# Sheet2.net
KiCad netlist of a schematic drawn in Altium Designer
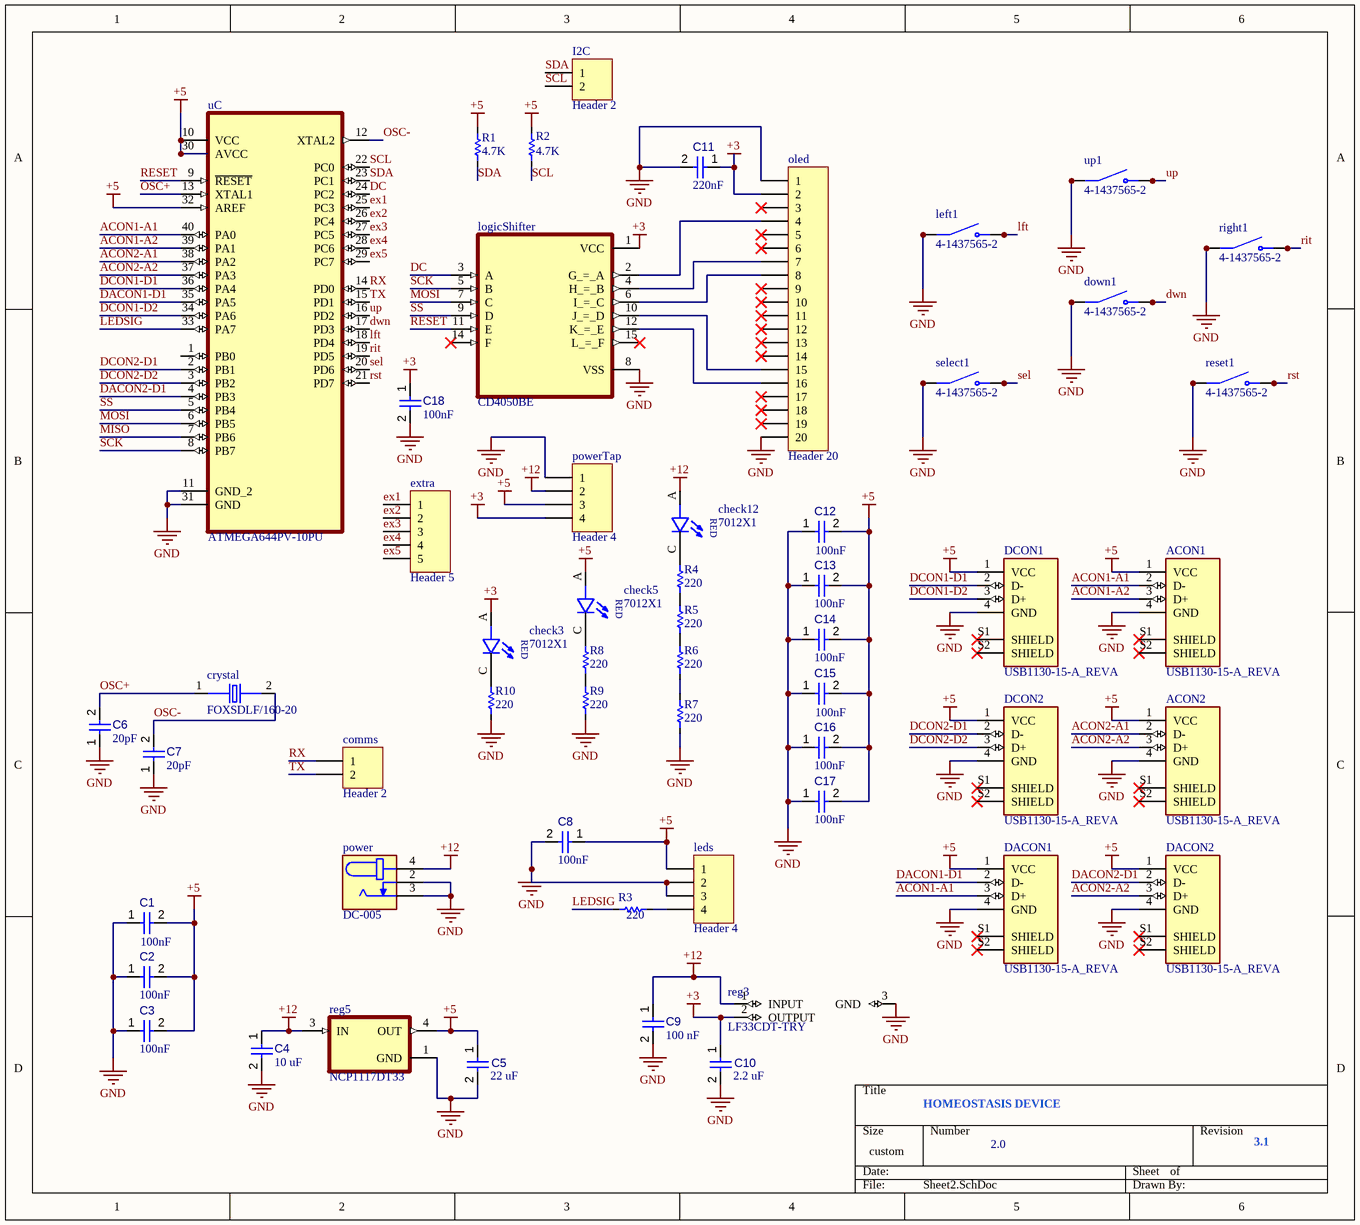
[diagram p0: Sheet2.SchDoc]

(export (version "E")
  (design (tool "Eeschema 10.0.6"))
  (components
    (comp (ref "ACON1")
      (value "USB1130-15-A_REVA")
      (footprint "GCT_USB1130-15-A_REVA")
      (fields (field (name "MF") "{'manufacturer': u'Global Connector Technology'}"))
      (libsource (lib "SnapEDA_Library") (part "USB1130-15-A_REVA"))
    )
    (comp (ref "ACON2")
      (value "USB1130-15-A_REVA")
      (footprint "GCT_USB1130-15-A_REVA")
      (fields (field (name "MF") "{'manufacturer': u'Global Connector Technology'}"))
      (libsource (lib "SnapEDA_Library") (part "USB1130-15-A_REVA"))
    )
    (comp (ref "C1")
      (value "100nF")
      (footprint "CAPC0805(2012)145_L")
      (description "Chip Capacitor, 4.7µF +/-40%, 25V, 0805, Thickness 1.45 mm")
      (fields (field (name "TOLERANCE") "20%") (field (name "Comment") "Capacitor 4.7µF +/-40% 25V 0805"))
      (libsource (lib "University of Minnesota - Solar Vehicle Project") (part "CAP-NP-2"))
    )
    (comp (ref "C2")
      (value "100nF")
      (footprint "CAPC0805(2012)145_L")
      (description "Chip Capacitor, 4.7µF +/-40%, 25V, 0805, Thickness 1.45 mm")
      (fields (field (name "TOLERANCE") "20%") (field (name "Comment") "Capacitor 4.7µF +/-40% 25V 0805"))
      (libsource (lib "University of Minnesota - Solar Vehicle Project") (part "CAP-NP-2"))
    )
    (comp (ref "C3")
      (value "100nF")
      (footprint "CAPC0805(2012)145_L")
      (description "Chip Capacitor, 4.7µF +/-40%, 25V, 0805, Thickness 1.45 mm")
      (fields (field (name "TOLERANCE") "20%") (field (name "Comment") "Capacitor 4.7µF +/-40% 25V 0805"))
      (libsource (lib "University of Minnesota - Solar Vehicle Project") (part "CAP-NP-2"))
    )
    (comp (ref "C4")
      (value "10 uF")
      (footprint "CAPC0805(2012)145_L")
      (description "Chip Capacitor, 4.7µF +/-40%, 25V, 0805, Thickness 1.45 mm")
      (fields (field (name "TOLERANCE") "20%") (field (name "Comment") "Capacitor 4.7µF +/-40% 25V 0805"))
      (libsource (lib "University of Minnesota - Solar Vehicle Project") (part "CAP-NP-2"))
    )
    (comp (ref "C5")
      (value "22 uF")
      (footprint "CAPC0805(2012)145_L")
      (description "Chip Capacitor, 4.7µF +/-40%, 25V, 0805, Thickness 1.45 mm")
      (fields (field (name "TOLERANCE") "20%") (field (name "Comment") "Capacitor 4.7µF +/-40% 25V 0805"))
      (libsource (lib "University of Minnesota - Solar Vehicle Project") (part "CAP-NP-2"))
    )
    (comp (ref "C6")
      (value "20pF")
      (footprint "CAPC2013X135X45ML10T25")
      (description "Chip Capacitor, 1 uF, +/- 10%, 50 V, 0805 (2012 Metric)")
      (fields (field (name "TOLERANCE") "10%") (field (name "Comment") "Capacitor 1 uF +/- 10% 50 V 0805"))
      (libsource (lib "University of Minnesota - Solar Vehicle Project") (part "CAP-NP-2"))
    )
    (comp (ref "C7")
      (value "20pF")
      (footprint "CAPC2013X135X45ML10T25")
      (description "Chip Capacitor, 1 uF, +/- 10%, 50 V, 0805 (2012 Metric)")
      (fields (field (name "TOLERANCE") "10%") (field (name "Comment") "Capacitor 1 uF +/- 10% 50 V 0805"))
      (libsource (lib "University of Minnesota - Solar Vehicle Project") (part "CAP-NP-2"))
    )
    (comp (ref "C8")
      (value "100nF")
      (footprint "CAPC0805(2012)145_L")
      (description "Chip Capacitor, 4.7µF +/-40%, 25V, 0805, Thickness 1.45 mm")
      (fields (field (name "TOLERANCE") "20%") (field (name "Comment") "Capacitor 4.7µF +/-40% 25V 0805"))
      (libsource (lib "University of Minnesota - Solar Vehicle Project") (part "CAP-NP-2"))
    )
    (comp (ref "C9")
      (value "100 nF")
      (footprint "CAPC0805(2012)145_L")
      (description "Chip Capacitor, 4.7µF +/-40%, 25V, 0805, Thickness 1.45 mm")
      (fields (field (name "TOLERANCE") "20%") (field (name "Comment") "Capacitor 4.7µF +/-40% 25V 0805"))
      (libsource (lib "University of Minnesota - Solar Vehicle Project") (part "CAP-NP-2"))
    )
    (comp (ref "C10")
      (value "2.2 uF")
      (footprint "CAPC0805(2012)145_L")
      (description "Chip Capacitor, 4.7µF +/-40%, 25V, 0805, Thickness 1.45 mm")
      (fields (field (name "TOLERANCE") "20%") (field (name "Comment") "Capacitor 4.7µF +/-40% 25V 0805"))
      (libsource (lib "University of Minnesota - Solar Vehicle Project") (part "CAP-NP-2"))
    )
    (comp (ref "C11")
      (value "220nF")
      (footprint "CAPC0805(2012)145_L")
      (description "Chip Capacitor, 4.7µF +/-40%, 25V, 0805, Thickness 1.45 mm")
      (fields (field (name "TOLERANCE") "20%") (field (name "Comment") "Capacitor 4.7µF +/-40% 25V 0805"))
      (libsource (lib "University of Minnesota - Solar Vehicle Project") (part "CAP-NP-2"))
    )
    (comp (ref "C12")
      (value "100nF")
      (footprint "CAPC0805(2012)145_L")
      (description "Chip Capacitor, 4.7µF +/-40%, 25V, 0805, Thickness 1.45 mm")
      (fields (field (name "TOLERANCE") "20%") (field (name "Comment") "Capacitor 4.7µF +/-40% 25V 0805"))
      (libsource (lib "University of Minnesota - Solar Vehicle Project") (part "CAP-NP-2"))
    )
    (comp (ref "C13")
      (value "100nF")
      (footprint "CAPC0805(2012)145_L")
      (description "Chip Capacitor, 4.7µF +/-40%, 25V, 0805, Thickness 1.45 mm")
      (fields (field (name "TOLERANCE") "20%") (field (name "Comment") "Capacitor 4.7µF +/-40% 25V 0805"))
      (libsource (lib "University of Minnesota - Solar Vehicle Project") (part "CAP-NP-2"))
    )
    (comp (ref "C14")
      (value "100nF")
      (footprint "CAPC0805(2012)145_L")
      (description "Chip Capacitor, 4.7µF +/-40%, 25V, 0805, Thickness 1.45 mm")
      (fields (field (name "TOLERANCE") "20%") (field (name "Comment") "Capacitor 4.7µF +/-40% 25V 0805"))
      (libsource (lib "University of Minnesota - Solar Vehicle Project") (part "CAP-NP-2"))
    )
    (comp (ref "C15")
      (value "100nF")
      (footprint "CAPC0805(2012)145_L")
      (description "Chip Capacitor, 4.7µF +/-40%, 25V, 0805, Thickness 1.45 mm")
      (fields (field (name "TOLERANCE") "20%") (field (name "Comment") "Capacitor 4.7µF +/-40% 25V 0805"))
      (libsource (lib "University of Minnesota - Solar Vehicle Project") (part "CAP-NP-2"))
    )
    (comp (ref "C16")
      (value "100nF")
      (footprint "CAPC0805(2012)145_L")
      (description "Chip Capacitor, 4.7µF +/-40%, 25V, 0805, Thickness 1.45 mm")
      (fields (field (name "TOLERANCE") "20%") (field (name "Comment") "Capacitor 4.7µF +/-40% 25V 0805"))
      (libsource (lib "University of Minnesota - Solar Vehicle Project") (part "CAP-NP-2"))
    )
    (comp (ref "C17")
      (value "100nF")
      (footprint "CAPC0805(2012)145_L")
      (description "Chip Capacitor, 4.7µF +/-40%, 25V, 0805, Thickness 1.45 mm")
      (fields (field (name "TOLERANCE") "20%") (field (name "Comment") "Capacitor 4.7µF +/-40% 25V 0805"))
      (libsource (lib "University of Minnesota - Solar Vehicle Project") (part "CAP-NP-2"))
    )
    (comp (ref "C18")
      (value "100nF")
      (footprint "CAPC0805(2012)145_L")
      (description "Chip Capacitor, 4.7µF +/-40%, 25V, 0805, Thickness 1.45 mm")
      (fields (field (name "TOLERANCE") "20%") (field (name "Comment") "Capacitor 4.7µF +/-40% 25V 0805"))
      (libsource (lib "University of Minnesota - Solar Vehicle Project") (part "CAP-NP-2"))
    )
    (comp (ref "check3")
      (value "7012X1")
      (footprint "LED_7012X1")
      (description "Red LED Indication - Discrete 1.7V 0805 (2012 Metric)")
      (fields (field (name "MF") "{'manufacturer': u'Visual'}"))
      (libsource (lib "SnapEDA_Library") (part "7012X1"))
    )
    (comp (ref "check5")
      (value "7012X1")
      (footprint "LED_7012X1")
      (description "Red LED Indication - Discrete 1.7V 0805 (2012 Metric)")
      (fields (field (name "MF") "{'manufacturer': u'Visual'}"))
      (libsource (lib "SnapEDA_Library") (part "7012X1"))
    )
    (comp (ref "check12")
      (value "7012X1")
      (footprint "LED_7012X1")
      (description "Red LED Indication - Discrete 1.7V 0805 (2012 Metric)")
      (fields (field (name "MF") "{'manufacturer': u'Visual'}"))
      (libsource (lib "SnapEDA_Library") (part "7012X1"))
    )
    (comp (ref "comms")
      (value "Header 2")
      (footprint "HDR1X2")
      (description "Header, 2-Pin")
      (fields (field (name "PUBLISHER") "Altium Limited"))
      (libsource (lib "Miscellaneous Connectors") (part "Header 2"))
    )
    (comp (ref "crystal")
      (value "FOXSDLF/160-20")
      (footprint "XTAL_FOXSDLF/160-20")
      (description "Crystal 16MHz 20pF 2-Pin HC-49/SD")
      (fields (field (name "MF") "{'manufacturer': u'Fox Electronics'}"))
      (libsource (lib "SnapEDA_Library") (part "FOXSDLF/160-20"))
    )
    (comp (ref "DACON1")
      (value "USB1130-15-A_REVA")
      (footprint "GCT_USB1130-15-A_REVA")
      (fields (field (name "MF") "{'manufacturer': u'Global Connector Technology'}"))
      (libsource (lib "SnapEDA_Library") (part "USB1130-15-A_REVA"))
    )
    (comp (ref "DACON2")
      (value "USB1130-15-A_REVA")
      (footprint "GCT_USB1130-15-A_REVA")
      (fields (field (name "MF") "{'manufacturer': u'Global Connector Technology'}"))
      (libsource (lib "SnapEDA_Library") (part "USB1130-15-A_REVA"))
    )
    (comp (ref "DCON1")
      (value "USB1130-15-A_REVA")
      (footprint "GCT_USB1130-15-A_REVA")
      (fields (field (name "MF") "{'manufacturer': u'Global Connector Technology'}"))
      (libsource (lib "SnapEDA_Library") (part "USB1130-15-A_REVA"))
    )
    (comp (ref "DCON2")
      (value "USB1130-15-A_REVA")
      (footprint "GCT_USB1130-15-A_REVA")
      (fields (field (name "MF") "{'manufacturer': u'Global Connector Technology'}"))
      (libsource (lib "SnapEDA_Library") (part "USB1130-15-A_REVA"))
    )
    (comp (ref "down1")
      (value "4-1437565-2")
      (footprint "SW_4-1437565-2")
      (fields (field (name "MF") "{'manufacturer': u'TE Connectivity'}"))
      (libsource (lib "SnapEDA_Library") (part "4-1437565-2"))
    )
    (comp (ref "extra")
      (value "Header 5")
      (footprint "HDR1X5")
      (description "Header, 5-Pin")
      (fields (field (name "PUBLISHER") "Altium Limited"))
      (libsource (lib "Miscellaneous Connectors") (part "Header 5"))
    )
    (comp (ref "I2C")
      (value "Header 2")
      (footprint "HDR1X2")
      (description "Header, 2-Pin")
      (fields (field (name "PUBLISHER") "Altium Limited"))
      (libsource (lib "Miscellaneous Connectors") (part "Header 2"))
    )
    (comp (ref "leds")
      (value "Header 4")
      (footprint "HDR1X4")
      (description "Header, 4-Pin")
      (fields (field (name "PUBLISHER") "Altium Limited"))
      (libsource (lib "Miscellaneous Connectors") (part "Header 4"))
    )
    (comp (ref "left1")
      (value "4-1437565-2")
      (footprint "SW_4-1437565-2")
      (fields (field (name "MF") "{'manufacturer': u'TE Connectivity'}"))
      (libsource (lib "SnapEDA_Library") (part "4-1437565-2"))
    )
    (comp (ref "logicShifter")
      (value "CD4050BE")
      (footprint "DIP794W45P254L1969H508Q16")
      (fields (field (name "MF") "{'manufacturer': u'Texas Instruments'}"))
      (libsource (lib "SnapEDA_Library") (part "CD4050BE"))
    )
    (comp (ref "oled")
      (value "Header 20")
      (footprint "HDR1X20")
      (description "Header, 20-Pin")
      (fields (field (name "PUBLISHER") "Altium Limited"))
      (libsource (lib "Miscellaneous Connectors") (part "Header 20"))
    )
    (comp (ref "power")
      (value "DC-005")
      (footprint "NINIGI_DC-005")
      (description "DC Jack")
      (fields (field (name "MF") "{'manufacturer': u'Best Inc.'}"))
      (libsource (lib "SnapEDA_Library") (part "DC-005"))
    )
    (comp (ref "powerTap")
      (value "Header 4")
      (footprint "HDR1X4")
      (description "Header, 4-Pin")
      (fields (field (name "PUBLISHER") "Altium Limited"))
      (libsource (lib "Miscellaneous Connectors") (part "Header 4"))
    )
    (comp (ref "R1")
      (value "4.7K")
      (footprint "0805_Resistor")
      (description "RES 4.7K OHM 1/8W 1% 0805 SMD")
      (fields
        (field (name "MANUFACTURER") "Yageo")
        (field (name "MANUFACTURER PART NUMBER") "AC0805FR-074K7L")
        (field (name "SVP CREATOR") "Andrew Wu")
      )
      (libsource (lib "University of Minnesota - Solar Vehicle Project") (part "Symbol"))
    )
    (comp (ref "R2")
      (value "4.7K")
      (footprint "0805_Resistor")
      (description "RES 4.7K OHM 1/8W 1% 0805 SMD")
      (fields
        (field (name "MANUFACTURER") "Yageo")
        (field (name "MANUFACTURER PART NUMBER") "AC0805FR-074K7L")
        (field (name "SVP CREATOR") "Andrew Wu")
      )
      (libsource (lib "University of Minnesota - Solar Vehicle Project") (part "Symbol"))
    )
    (comp (ref "R3")
      (value "220")
      (footprint "0805_Resistor")
      (description "RES 4.7K OHM 1/8W 1% 0805 SMD")
      (fields
        (field (name "MANUFACTURER") "Yageo")
        (field (name "MANUFACTURER PART NUMBER") "AC0805FR-074K7L")
        (field (name "SVP CREATOR") "Andrew Wu")
      )
      (libsource (lib "University of Minnesota - Solar Vehicle Project") (part "Symbol"))
    )
    (comp (ref "R4")
      (value "220")
      (footprint "0805_Resistor")
      (description "RES 4.7K OHM 1/8W 1% 0805 SMD")
      (fields
        (field (name "MANUFACTURER") "Yageo")
        (field (name "MANUFACTURER PART NUMBER") "AC0805FR-074K7L")
        (field (name "SVP CREATOR") "Andrew Wu")
      )
      (libsource (lib "University of Minnesota - Solar Vehicle Project") (part "Symbol"))
    )
    (comp (ref "R5")
      (value "220")
      (footprint "0805_Resistor")
      (description "RES 4.7K OHM 1/8W 1% 0805 SMD")
      (fields
        (field (name "MANUFACTURER") "Yageo")
        (field (name "MANUFACTURER PART NUMBER") "AC0805FR-074K7L")
        (field (name "SVP CREATOR") "Andrew Wu")
      )
      (libsource (lib "University of Minnesota - Solar Vehicle Project") (part "Symbol"))
    )
    (comp (ref "R6")
      (value "220")
      (footprint "0805_Resistor")
      (description "RES 4.7K OHM 1/8W 1% 0805 SMD")
      (fields
        (field (name "MANUFACTURER") "Yageo")
        (field (name "MANUFACTURER PART NUMBER") "AC0805FR-074K7L")
        (field (name "SVP CREATOR") "Andrew Wu")
      )
      (libsource (lib "University of Minnesota - Solar Vehicle Project") (part "Symbol"))
    )
    (comp (ref "R7")
      (value "220")
      (footprint "0805_Resistor")
      (description "RES 4.7K OHM 1/8W 1% 0805 SMD")
      (fields
        (field (name "MANUFACTURER") "Yageo")
        (field (name "MANUFACTURER PART NUMBER") "AC0805FR-074K7L")
        (field (name "SVP CREATOR") "Andrew Wu")
      )
      (libsource (lib "University of Minnesota - Solar Vehicle Project") (part "Symbol"))
    )
    (comp (ref "R8")
      (value "220")
      (footprint "0805_Resistor")
      (description "RES 4.7K OHM 1/8W 1% 0805 SMD")
      (fields
        (field (name "MANUFACTURER") "Yageo")
        (field (name "MANUFACTURER PART NUMBER") "AC0805FR-074K7L")
        (field (name "SVP CREATOR") "Andrew Wu")
      )
      (libsource (lib "University of Minnesota - Solar Vehicle Project") (part "Symbol"))
    )
    (comp (ref "R9")
      (value "220")
      (footprint "0805_Resistor")
      (description "RES 4.7K OHM 1/8W 1% 0805 SMD")
      (fields
        (field (name "MANUFACTURER") "Yageo")
        (field (name "MANUFACTURER PART NUMBER") "AC0805FR-074K7L")
        (field (name "SVP CREATOR") "Andrew Wu")
      )
      (libsource (lib "University of Minnesota - Solar Vehicle Project") (part "Symbol"))
    )
    (comp (ref "R10")
      (value "220")
      (footprint "0805_Resistor")
      (description "RES 4.7K OHM 1/8W 1% 0805 SMD")
      (fields
        (field (name "MANUFACTURER") "Yageo")
        (field (name "MANUFACTURER PART NUMBER") "AC0805FR-074K7L")
        (field (name "SVP CREATOR") "Andrew Wu")
      )
      (libsource (lib "University of Minnesota - Solar Vehicle Project") (part "Symbol"))
    )
    (comp (ref "reg3")
      (value "LF33CDT-TRY")
      (footprint "LD1117DT33")
      (fields (field (name "MF") "{'manufacturer': u'STMicroelectronics'}"))
      (libsource (lib "SnapEDA_Library") (part "LF33CDT-TRY"))
    )
    (comp (ref "reg5")
      (value "NCP1117DT33")
      (footprint "VREG_NCP1117DT33")
      (description "1.0 A Positive LDO Linear Voltage Regulator (Fixed and Adjustable) Vout: 3.3 V")
      (fields (field (name "MF") "{'manufacturer': u'ON Semiconductor'}"))
      (libsource (lib "SnapEDA_Library") (part "NCP1117DT33"))
    )
    (comp (ref "reset1")
      (value "4-1437565-2")
      (footprint "SW_4-1437565-2")
      (fields (field (name "MF") "{'manufacturer': u'TE Connectivity'}"))
      (libsource (lib "SnapEDA_Library") (part "4-1437565-2"))
    )
    (comp (ref "right1")
      (value "4-1437565-2")
      (footprint "SW_4-1437565-2")
      (fields (field (name "MF") "{'manufacturer': u'TE Connectivity'}"))
      (libsource (lib "SnapEDA_Library") (part "4-1437565-2"))
    )
    (comp (ref "select1")
      (value "4-1437565-2")
      (footprint "SW_4-1437565-2")
      (fields (field (name "MF") "{'manufacturer': u'TE Connectivity'}"))
      (libsource (lib "SnapEDA_Library") (part "4-1437565-2"))
    )
    (comp (ref "uC")
      (value "ATMEGA644PV-10PU")
      (footprint "DIP254P1524X483-40")
      (description "8-bit Microcontroller with In-System Programmable  Flash")
      (fields (field (name "MF") "{'manufacturer': u'Microchip Technology'}"))
      (libsource (lib "SnapEDA_Library") (part "ATMEGA644PV-10PU"))
    )
    (comp (ref "up1")
      (value "4-1437565-2")
      (footprint "SW_4-1437565-2")
      (fields (field (name "MF") "{'manufacturer': u'TE Connectivity'}"))
      (libsource (lib "SnapEDA_Library") (part "4-1437565-2"))
    )
  )
  (nets
    (net (code "1") (name "+3") (class "Default")
      (node (ref "C10") (pin "1") (pinfunction "1_1") (pintype "passive"))
      (node (ref "C11") (pin "1") (pinfunction "1_1") (pintype "passive"))
      (node (ref "C18") (pin "1") (pinfunction "1_1") (pintype "passive"))
      (node (ref "check3") (pin "A") (pinfunction "A_A") (pintype "passive"))
      (node (ref "logicShifter") (pin "1") (pinfunction "VCC_1") (pintype "power_in"))
      (node (ref "oled") (pin "2") (pinfunction "2_2") (pintype "passive"))
      (node (ref "powerTap") (pin "4") (pinfunction "4_4") (pintype "passive"))
      (node (ref "reg3") (pin "2") (pinfunction "OUTPUT_2") (pintype "bidirectional"))
    )
    (net (code "2") (name "+5") (class "Default")
      (node (ref "ACON1") (pin "1") (pinfunction "VCC_1") (pintype "power_in"))
      (node (ref "ACON2") (pin "1") (pinfunction "VCC_1") (pintype "power_in"))
      (node (ref "C1") (pin "2") (pinfunction "2_2") (pintype "passive"))
      (node (ref "C12") (pin "2") (pinfunction "2_2") (pintype "passive"))
      (node (ref "C13") (pin "2") (pinfunction "2_2") (pintype "passive"))
      (node (ref "C14") (pin "2") (pinfunction "2_2") (pintype "passive"))
      (node (ref "C15") (pin "2") (pinfunction "2_2") (pintype "passive"))
      (node (ref "C16") (pin "2") (pinfunction "2_2") (pintype "passive"))
      (node (ref "C17") (pin "2") (pinfunction "2_2") (pintype "passive"))
      (node (ref "C2") (pin "2") (pinfunction "2_2") (pintype "passive"))
      (node (ref "C3") (pin "2") (pinfunction "2_2") (pintype "passive"))
      (node (ref "C5") (pin "1") (pinfunction "1_1") (pintype "passive"))
      (node (ref "C8") (pin "1") (pinfunction "1_1") (pintype "passive"))
      (node (ref "DACON1") (pin "1") (pinfunction "VCC_1") (pintype "power_in"))
      (node (ref "DACON2") (pin "1") (pinfunction "VCC_1") (pintype "power_in"))
      (node (ref "DCON1") (pin "1") (pinfunction "VCC_1") (pintype "power_in"))
      (node (ref "DCON2") (pin "1") (pinfunction "VCC_1") (pintype "power_in"))
      (node (ref "R1") (pin "1") (pinfunction "1_1") (pintype "passive"))
      (node (ref "R2") (pin "1") (pinfunction "1_1") (pintype "passive"))
      (node (ref "check5") (pin "A") (pinfunction "A_A") (pintype "passive"))
      (node (ref "leds") (pin "1") (pinfunction "1_1") (pintype "passive"))
      (node (ref "powerTap") (pin "3") (pinfunction "3_3") (pintype "passive"))
      (node (ref "reg5") (pin "4") (pinfunction "OUT_4") (pintype "output"))
      (node (ref "uC") (pin "10") (pinfunction "VCC_10") (pintype "power_in"))
      (node (ref "uC") (pin "30") (pinfunction "AVCC_30") (pintype "power_in"))
      (node (ref "uC") (pin "32") (pinfunction "AREF_32") (pintype "input"))
    )
    (net (code "3") (name "+12") (class "Default")
      (node (ref "C4") (pin "1") (pinfunction "1_1") (pintype "passive"))
      (node (ref "C9") (pin "1") (pinfunction "1_1") (pintype "passive"))
      (node (ref "check12") (pin "A") (pinfunction "A_A") (pintype "passive"))
      (node (ref "power") (pin "4") (pinfunction "2_4") (pintype "passive"))
      (node (ref "powerTap") (pin "2") (pinfunction "2_2") (pintype "passive"))
      (node (ref "reg3") (pin "1") (pinfunction "INPUT_1") (pintype "bidirectional"))
      (node (ref "reg5") (pin "3") (pinfunction "IN_3") (pintype "input"))
    )
    (net (code "4") (name "/ACON1-A1") (class "Default")
      (node (ref "ACON1") (pin "2") (pinfunction "D-_2") (pintype "bidirectional"))
      (node (ref "DACON1") (pin "3") (pinfunction "D+_3") (pintype "bidirectional"))
      (node (ref "uC") (pin "40") (pinfunction "PA0_40") (pintype "bidirectional"))
    )
    (net (code "5") (name "/ACON1-A2") (class "Default")
      (node (ref "ACON1") (pin "3") (pinfunction "D+_3") (pintype "bidirectional"))
      (node (ref "uC") (pin "39") (pinfunction "PA1_39") (pintype "bidirectional"))
    )
    (net (code "6") (name "/ACON2-A1") (class "Default")
      (node (ref "ACON2") (pin "2") (pinfunction "D-_2") (pintype "bidirectional"))
      (node (ref "uC") (pin "38") (pinfunction "PA2_38") (pintype "bidirectional"))
    )
    (net (code "7") (name "/ACON2-A2") (class "Default")
      (node (ref "ACON2") (pin "3") (pinfunction "D+_3") (pintype "bidirectional"))
      (node (ref "DACON2") (pin "3") (pinfunction "D+_3") (pintype "bidirectional"))
      (node (ref "uC") (pin "37") (pinfunction "PA3_37") (pintype "bidirectional"))
    )
    (net (code "8") (name "/DACON1-D1") (class "Default")
      (node (ref "DACON1") (pin "2") (pinfunction "D-_2") (pintype "bidirectional"))
      (node (ref "uC") (pin "35") (pinfunction "PA5_35") (pintype "bidirectional"))
    )
    (net (code "9") (name "/DACON2-D1") (class "Default")
      (node (ref "DACON2") (pin "2") (pinfunction "D-_2") (pintype "bidirectional"))
      (node (ref "uC") (pin "4") (pinfunction "PB3_4") (pintype "bidirectional"))
    )
    (net (code "10") (name "/DC") (class "Default")
      (node (ref "logicShifter") (pin "3") (pinfunction "A_3") (pintype "input"))
      (node (ref "uC") (pin "24") (pinfunction "PC2_24") (pintype "bidirectional"))
    )
    (net (code "11") (name "/DCON1-D1") (class "Default")
      (node (ref "DCON1") (pin "2") (pinfunction "D-_2") (pintype "bidirectional"))
      (node (ref "uC") (pin "36") (pinfunction "PA4_36") (pintype "bidirectional"))
    )
    (net (code "12") (name "/DCON1-D2") (class "Default")
      (node (ref "DCON1") (pin "3") (pinfunction "D+_3") (pintype "bidirectional"))
      (node (ref "uC") (pin "34") (pinfunction "PA6_34") (pintype "bidirectional"))
    )
    (net (code "13") (name "/DCON2-D1") (class "Default")
      (node (ref "DCON2") (pin "2") (pinfunction "D-_2") (pintype "bidirectional"))
      (node (ref "uC") (pin "2") (pinfunction "PB1_2") (pintype "bidirectional"))
    )
    (net (code "14") (name "/DCON2-D2") (class "Default")
      (node (ref "DCON2") (pin "3") (pinfunction "D+_3") (pintype "bidirectional"))
      (node (ref "uC") (pin "3") (pinfunction "PB2_3") (pintype "bidirectional"))
    )
    (net (code "15") (name "/LEDSIG") (class "Default")
      (node (ref "R3") (pin "1") (pinfunction "1_1") (pintype "passive"))
      (node (ref "uC") (pin "33") (pinfunction "PA7_33") (pintype "bidirectional"))
    )
    (net (code "16") (name "/MISO") (class "Default")
      (node (ref "uC") (pin "7") (pinfunction "PB6_7") (pintype "bidirectional"))
    )
    (net (code "17") (name "/MOSI") (class "Default")
      (node (ref "logicShifter") (pin "7") (pinfunction "C_7") (pintype "input"))
      (node (ref "uC") (pin "6") (pinfunction "PB5_6") (pintype "bidirectional"))
    )
    (net (code "18") (name "/OSC+") (class "Default")
      (node (ref "C6") (pin "2") (pinfunction "2_2") (pintype "passive"))
      (node (ref "crystal") (pin "1") (pinfunction "1_1") (pintype "passive"))
      (node (ref "uC") (pin "13") (pinfunction "XTAL1_13") (pintype "input"))
    )
    (net (code "19") (name "/OSC-") (class "Default")
      (node (ref "C7") (pin "2") (pinfunction "2_2") (pintype "passive"))
      (node (ref "crystal") (pin "2") (pinfunction "2_2") (pintype "passive"))
      (node (ref "uC") (pin "12") (pinfunction "XTAL2_12") (pintype "output"))
    )
    (net (code "20") (name "/RESET") (class "Default")
      (node (ref "logicShifter") (pin "11") (pinfunction "E_11") (pintype "input"))
      (node (ref "uC") (pin "9") (pinfunction "~{RESET}_9") (pintype "input"))
    )
    (net (code "21") (name "/RX") (class "Default")
      (node (ref "comms") (pin "1") (pinfunction "1_1") (pintype "passive"))
      (node (ref "uC") (pin "14") (pinfunction "PD0_14") (pintype "bidirectional"))
    )
    (net (code "22") (name "/SCK") (class "Default")
      (node (ref "logicShifter") (pin "5") (pinfunction "B_5") (pintype "input"))
      (node (ref "uC") (pin "8") (pinfunction "PB7_8") (pintype "bidirectional"))
    )
    (net (code "23") (name "/SCL") (class "Default")
      (node (ref "I2C") (pin "2") (pinfunction "2_2") (pintype "passive"))
      (node (ref "R2") (pin "2") (pinfunction "2_2") (pintype "passive"))
      (node (ref "uC") (pin "22") (pinfunction "PC0_22") (pintype "bidirectional"))
    )
    (net (code "24") (name "/SDA") (class "Default")
      (node (ref "I2C") (pin "1") (pinfunction "1_1") (pintype "passive"))
      (node (ref "R1") (pin "2") (pinfunction "2_2") (pintype "passive"))
      (node (ref "uC") (pin "23") (pinfunction "PC1_23") (pintype "bidirectional"))
    )
    (net (code "25") (name "/SS") (class "Default")
      (node (ref "logicShifter") (pin "9") (pinfunction "D_9") (pintype "input"))
      (node (ref "uC") (pin "5") (pinfunction "PB4_5") (pintype "bidirectional"))
    )
    (net (code "26") (name "/TX") (class "Default")
      (node (ref "comms") (pin "2") (pinfunction "2_2") (pintype "passive"))
      (node (ref "uC") (pin "15") (pinfunction "PD1_15") (pintype "bidirectional"))
    )
    (net (code "27") (name "/dwn") (class "Default")
      (node (ref "down1") (pin "3") (pinfunction "NO_3") (pintype "passive"))
      (node (ref "down1") (pin "4") (pinfunction "NO_4") (pintype "passive"))
      (node (ref "uC") (pin "17") (pinfunction "PD3_17") (pintype "bidirectional"))
    )
    (net (code "28") (name "/ex1") (class "Default")
      (node (ref "extra") (pin "1") (pinfunction "1_1") (pintype "passive"))
      (node (ref "uC") (pin "25") (pinfunction "PC3_25") (pintype "bidirectional"))
    )
    (net (code "29") (name "/ex2") (class "Default")
      (node (ref "extra") (pin "2") (pinfunction "2_2") (pintype "passive"))
      (node (ref "uC") (pin "26") (pinfunction "PC4_26") (pintype "bidirectional"))
    )
    (net (code "30") (name "/ex3") (class "Default")
      (node (ref "extra") (pin "3") (pinfunction "3_3") (pintype "passive"))
      (node (ref "uC") (pin "27") (pinfunction "PC5_27") (pintype "bidirectional"))
    )
    (net (code "31") (name "/ex4") (class "Default")
      (node (ref "extra") (pin "4") (pinfunction "4_4") (pintype "passive"))
      (node (ref "uC") (pin "28") (pinfunction "PC6_28") (pintype "bidirectional"))
    )
    (net (code "32") (name "/ex5") (class "Default")
      (node (ref "extra") (pin "5") (pinfunction "5_5") (pintype "passive"))
      (node (ref "uC") (pin "29") (pinfunction "PC7_29") (pintype "bidirectional"))
    )
    (net (code "33") (name "/lft") (class "Default")
      (node (ref "left1") (pin "3") (pinfunction "NO_3") (pintype "passive"))
      (node (ref "left1") (pin "4") (pinfunction "NO_4") (pintype "passive"))
      (node (ref "uC") (pin "18") (pinfunction "PD4_18") (pintype "bidirectional"))
    )
    (net (code "34") (name "/rit") (class "Default")
      (node (ref "right1") (pin "3") (pinfunction "NO_3") (pintype "passive"))
      (node (ref "right1") (pin "4") (pinfunction "NO_4") (pintype "passive"))
      (node (ref "uC") (pin "19") (pinfunction "PD5_19") (pintype "bidirectional"))
    )
    (net (code "35") (name "/rst") (class "Default")
      (node (ref "reset1") (pin "3") (pinfunction "NO_3") (pintype "passive"))
      (node (ref "reset1") (pin "4") (pinfunction "NO_4") (pintype "passive"))
      (node (ref "uC") (pin "21") (pinfunction "PD7_21") (pintype "bidirectional"))
    )
    (net (code "36") (name "/sel") (class "Default")
      (node (ref "select1") (pin "3") (pinfunction "NO_3") (pintype "passive"))
      (node (ref "select1") (pin "4") (pinfunction "NO_4") (pintype "passive"))
      (node (ref "uC") (pin "20") (pinfunction "PD6_20") (pintype "bidirectional"))
    )
    (net (code "37") (name "/up") (class "Default")
      (node (ref "uC") (pin "16") (pinfunction "PD2_16") (pintype "bidirectional"))
      (node (ref "up1") (pin "3") (pinfunction "NO_3") (pintype "passive"))
      (node (ref "up1") (pin "4") (pinfunction "NO_4") (pintype "passive"))
    )
    (net (code "38") (name "GND") (class "Default")
      (node (ref "ACON1") (pin "4") (pinfunction "GND_4") (pintype "power_in"))
      (node (ref "ACON2") (pin "4") (pinfunction "GND_4") (pintype "power_in"))
      (node (ref "C1") (pin "1") (pinfunction "1_1") (pintype "passive"))
      (node (ref "C10") (pin "2") (pinfunction "2_2") (pintype "passive"))
      (node (ref "C11") (pin "2") (pinfunction "2_2") (pintype "passive"))
      (node (ref "C12") (pin "1") (pinfunction "1_1") (pintype "passive"))
      (node (ref "C13") (pin "1") (pinfunction "1_1") (pintype "passive"))
      (node (ref "C14") (pin "1") (pinfunction "1_1") (pintype "passive"))
      (node (ref "C15") (pin "1") (pinfunction "1_1") (pintype "passive"))
      (node (ref "C16") (pin "1") (pinfunction "1_1") (pintype "passive"))
      (node (ref "C17") (pin "1") (pinfunction "1_1") (pintype "passive"))
      (node (ref "C18") (pin "2") (pinfunction "2_2") (pintype "passive"))
      (node (ref "C2") (pin "1") (pinfunction "1_1") (pintype "passive"))
      (node (ref "C3") (pin "1") (pinfunction "1_1") (pintype "passive"))
      (node (ref "C4") (pin "2") (pinfunction "2_2") (pintype "passive"))
      (node (ref "C5") (pin "2") (pinfunction "2_2") (pintype "passive"))
      (node (ref "C6") (pin "1") (pinfunction "1_1") (pintype "passive"))
      (node (ref "C7") (pin "1") (pinfunction "1_1") (pintype "passive"))
      (node (ref "C8") (pin "2") (pinfunction "2_2") (pintype "passive"))
      (node (ref "C9") (pin "2") (pinfunction "2_2") (pintype "passive"))
      (node (ref "DACON1") (pin "4") (pinfunction "GND_4") (pintype "power_in"))
      (node (ref "DACON2") (pin "4") (pinfunction "GND_4") (pintype "power_in"))
      (node (ref "DCON1") (pin "4") (pinfunction "GND_4") (pintype "power_in"))
      (node (ref "DCON2") (pin "4") (pinfunction "GND_4") (pintype "power_in"))
      (node (ref "R10") (pin "1") (pinfunction "1_1") (pintype "passive"))
      (node (ref "R7") (pin "1") (pinfunction "1_1") (pintype "passive"))
      (node (ref "R9") (pin "1") (pinfunction "1_1") (pintype "passive"))
      (node (ref "down1") (pin "1") (pinfunction "COM_1") (pintype "passive"))
      (node (ref "down1") (pin "2") (pinfunction "COM_2") (pintype "passive"))
      (node (ref "leds") (pin "2") (pinfunction "2_2") (pintype "passive"))
      (node (ref "leds") (pin "3") (pinfunction "3_3") (pintype "passive"))
      (node (ref "left1") (pin "1") (pinfunction "COM_1") (pintype "passive"))
      (node (ref "left1") (pin "2") (pinfunction "COM_2") (pintype "passive"))
      (node (ref "logicShifter") (pin "8") (pinfunction "VSS_8") (pintype "power_in"))
      (node (ref "oled") (pin "1") (pinfunction "1_1") (pintype "passive"))
      (node (ref "oled") (pin "20") (pinfunction "20_20") (pintype "passive"))
      (node (ref "power") (pin "2") (pinfunction "4_2") (pintype "passive"))
      (node (ref "power") (pin "3") (pinfunction "5_3") (pintype "passive"))
      (node (ref "powerTap") (pin "1") (pinfunction "1_1") (pintype "passive"))
      (node (ref "reg3") (pin "3") (pinfunction "GND_3") (pintype "bidirectional"))
      (node (ref "reg5") (pin "1") (pinfunction "GND_1") (pintype "power_in"))
      (node (ref "reset1") (pin "1") (pinfunction "COM_1") (pintype "passive"))
      (node (ref "reset1") (pin "2") (pinfunction "COM_2") (pintype "passive"))
      (node (ref "right1") (pin "1") (pinfunction "COM_1") (pintype "passive"))
      (node (ref "right1") (pin "2") (pinfunction "COM_2") (pintype "passive"))
      (node (ref "select1") (pin "1") (pinfunction "COM_1") (pintype "passive"))
      (node (ref "select1") (pin "2") (pinfunction "COM_2") (pintype "passive"))
      (node (ref "uC") (pin "11") (pinfunction "GND_2_11") (pintype "passive"))
      (node (ref "uC") (pin "31") (pinfunction "GND_31") (pintype "passive"))
      (node (ref "up1") (pin "1") (pinfunction "COM_1") (pintype "passive"))
      (node (ref "up1") (pin "2") (pinfunction "COM_2") (pintype "passive"))
    )
    (net (code "39") (name "Net-(R3-Pad2)") (class "Default")
      (node (ref "R3") (pin "2") (pinfunction "2_2") (pintype "passive"))
      (node (ref "leds") (pin "4") (pinfunction "4_4") (pintype "passive"))
    )
    (net (code "40") (name "Net-(R4-Pad1)") (class "Default")
      (node (ref "R4") (pin "1") (pinfunction "1_1") (pintype "passive"))
      (node (ref "R5") (pin "2") (pinfunction "2_2") (pintype "passive"))
    )
    (net (code "41") (name "Net-(R4-Pad2)") (class "Default")
      (node (ref "R4") (pin "2") (pinfunction "2_2") (pintype "passive"))
      (node (ref "check12") (pin "C") (pinfunction "C_C") (pintype "passive"))
    )
    (net (code "42") (name "Net-(R5-Pad1)") (class "Default")
      (node (ref "R5") (pin "1") (pinfunction "1_1") (pintype "passive"))
      (node (ref "R6") (pin "2") (pinfunction "2_2") (pintype "passive"))
    )
    (net (code "43") (name "Net-(R6-Pad1)") (class "Default")
      (node (ref "R6") (pin "1") (pinfunction "1_1") (pintype "passive"))
      (node (ref "R7") (pin "2") (pinfunction "2_2") (pintype "passive"))
    )
    (net (code "44") (name "Net-(R8-Pad1)") (class "Default")
      (node (ref "R8") (pin "1") (pinfunction "1_1") (pintype "passive"))
      (node (ref "R9") (pin "2") (pinfunction "2_2") (pintype "passive"))
    )
    (net (code "45") (name "Net-(R8-Pad2)") (class "Default")
      (node (ref "R8") (pin "2") (pinfunction "2_2") (pintype "passive"))
      (node (ref "check5") (pin "C") (pinfunction "C_C") (pintype "passive"))
    )
    (net (code "46") (name "Net-(R10-Pad2)") (class "Default")
      (node (ref "R10") (pin "2") (pinfunction "2_2") (pintype "passive"))
      (node (ref "check3") (pin "C") (pinfunction "C_C") (pintype "passive"))
    )
    (net (code "47") (name "Net-(logicShifter-G_=_A)") (class "Default")
      (node (ref "logicShifter") (pin "2") (pinfunction "G_=_A_2") (pintype "output"))
      (node (ref "oled") (pin "4") (pinfunction "4_4") (pintype "passive"))
    )
    (net (code "48") (name "Net-(logicShifter-H_=_B)") (class "Default")
      (node (ref "logicShifter") (pin "4") (pinfunction "H_=_B_4") (pintype "output"))
      (node (ref "oled") (pin "7") (pinfunction "7_7") (pintype "passive"))
    )
    (net (code "49") (name "Net-(logicShifter-I_=_C)") (class "Default")
      (node (ref "logicShifter") (pin "6") (pinfunction "I_=_C_6") (pintype "output"))
      (node (ref "oled") (pin "8") (pinfunction "8_8") (pintype "passive"))
    )
    (net (code "50") (name "Net-(logicShifter-J_=_D)") (class "Default")
      (node (ref "logicShifter") (pin "10") (pinfunction "J_=_D_10") (pintype "output"))
      (node (ref "oled") (pin "15") (pinfunction "15_15") (pintype "passive"))
    )
    (net (code "51") (name "Net-(logicShifter-K_=_E)") (class "Default")
      (node (ref "logicShifter") (pin "12") (pinfunction "K_=_E_12") (pintype "output"))
      (node (ref "oled") (pin "16") (pinfunction "16_16") (pintype "passive"))
    )
    (net (code "52") (name "unconnected-(ACON1-SHIELD-PadS1)") (class "Default")
      (node (ref "ACON1") (pin "S1") (pinfunction "SHIELD_S1") (pintype "passive+no_connect"))
    )
    (net (code "53") (name "unconnected-(ACON1-SHIELD-PadS2)") (class "Default")
      (node (ref "ACON1") (pin "S2") (pinfunction "SHIELD_S2") (pintype "passive+no_connect"))
    )
    (net (code "54") (name "unconnected-(ACON2-SHIELD-PadS1)") (class "Default")
      (node (ref "ACON2") (pin "S1") (pinfunction "SHIELD_S1") (pintype "passive+no_connect"))
    )
    (net (code "55") (name "unconnected-(ACON2-SHIELD-PadS2)") (class "Default")
      (node (ref "ACON2") (pin "S2") (pinfunction "SHIELD_S2") (pintype "passive+no_connect"))
    )
    (net (code "56") (name "unconnected-(DACON1-SHIELD-PadS1)") (class "Default")
      (node (ref "DACON1") (pin "S1") (pinfunction "SHIELD_S1") (pintype "passive+no_connect"))
    )
    (net (code "57") (name "unconnected-(DACON1-SHIELD-PadS2)") (class "Default")
      (node (ref "DACON1") (pin "S2") (pinfunction "SHIELD_S2") (pintype "passive+no_connect"))
    )
    (net (code "58") (name "unconnected-(DACON2-SHIELD-PadS1)") (class "Default")
      (node (ref "DACON2") (pin "S1") (pinfunction "SHIELD_S1") (pintype "passive+no_connect"))
    )
    (net (code "59") (name "unconnected-(DACON2-SHIELD-PadS2)") (class "Default")
      (node (ref "DACON2") (pin "S2") (pinfunction "SHIELD_S2") (pintype "passive+no_connect"))
    )
    (net (code "60") (name "unconnected-(DCON1-SHIELD-PadS1)") (class "Default")
      (node (ref "DCON1") (pin "S1") (pinfunction "SHIELD_S1") (pintype "passive+no_connect"))
    )
    (net (code "61") (name "unconnected-(DCON1-SHIELD-PadS2)") (class "Default")
      (node (ref "DCON1") (pin "S2") (pinfunction "SHIELD_S2") (pintype "passive+no_connect"))
    )
    (net (code "62") (name "unconnected-(DCON2-SHIELD-PadS1)") (class "Default")
      (node (ref "DCON2") (pin "S1") (pinfunction "SHIELD_S1") (pintype "passive+no_connect"))
    )
    (net (code "63") (name "unconnected-(DCON2-SHIELD-PadS2)") (class "Default")
      (node (ref "DCON2") (pin "S2") (pinfunction "SHIELD_S2") (pintype "passive+no_connect"))
    )
    (net (code "64") (name "unconnected-(logicShifter-F-Pad14)") (class "Default")
      (node (ref "logicShifter") (pin "14") (pinfunction "F_14") (pintype "input+no_connect"))
    )
    (net (code "65") (name "unconnected-(logicShifter-L_=_F-Pad15)") (class "Default")
      (node (ref "logicShifter") (pin "15") (pinfunction "L_=_F_15") (pintype "output+no_connect"))
    )
    (net (code "66") (name "unconnected-(oled-Pad3)") (class "Default")
      (node (ref "oled") (pin "3") (pinfunction "3_3") (pintype "passive+no_connect"))
    )
    (net (code "67") (name "unconnected-(oled-Pad5)") (class "Default")
      (node (ref "oled") (pin "5") (pinfunction "5_5") (pintype "passive+no_connect"))
    )
    (net (code "68") (name "unconnected-(oled-Pad6)") (class "Default")
      (node (ref "oled") (pin "6") (pinfunction "6_6") (pintype "passive+no_connect"))
    )
    (net (code "69") (name "unconnected-(oled-Pad9)") (class "Default")
      (node (ref "oled") (pin "9") (pinfunction "9_9") (pintype "passive+no_connect"))
    )
    (net (code "70") (name "unconnected-(oled-Pad10)") (class "Default")
      (node (ref "oled") (pin "10") (pinfunction "10_10") (pintype "passive+no_connect"))
    )
    (net (code "71") (name "unconnected-(oled-Pad11)") (class "Default")
      (node (ref "oled") (pin "11") (pinfunction "11_11") (pintype "passive+no_connect"))
    )
    (net (code "72") (name "unconnected-(oled-Pad12)") (class "Default")
      (node (ref "oled") (pin "12") (pinfunction "12_12") (pintype "passive+no_connect"))
    )
    (net (code "73") (name "unconnected-(oled-Pad13)") (class "Default")
      (node (ref "oled") (pin "13") (pinfunction "13_13") (pintype "passive+no_connect"))
    )
    (net (code "74") (name "unconnected-(oled-Pad14)") (class "Default")
      (node (ref "oled") (pin "14") (pinfunction "14_14") (pintype "passive+no_connect"))
    )
    (net (code "75") (name "unconnected-(oled-Pad17)") (class "Default")
      (node (ref "oled") (pin "17") (pinfunction "17_17") (pintype "passive+no_connect"))
    )
    (net (code "76") (name "unconnected-(oled-Pad18)") (class "Default")
      (node (ref "oled") (pin "18") (pinfunction "18_18") (pintype "passive+no_connect"))
    )
    (net (code "77") (name "unconnected-(oled-Pad19)") (class "Default")
      (node (ref "oled") (pin "19") (pinfunction "19_19") (pintype "passive+no_connect"))
    )
    (net (code "78") (name "unconnected-(uC-PB0-Pad1)") (class "Default")
      (node (ref "uC") (pin "1") (pinfunction "PB0_1") (pintype "bidirectional"))
    )
  )
)
